# Keypad.net
KiCad netlist of a schematic drawn in Altium Designer
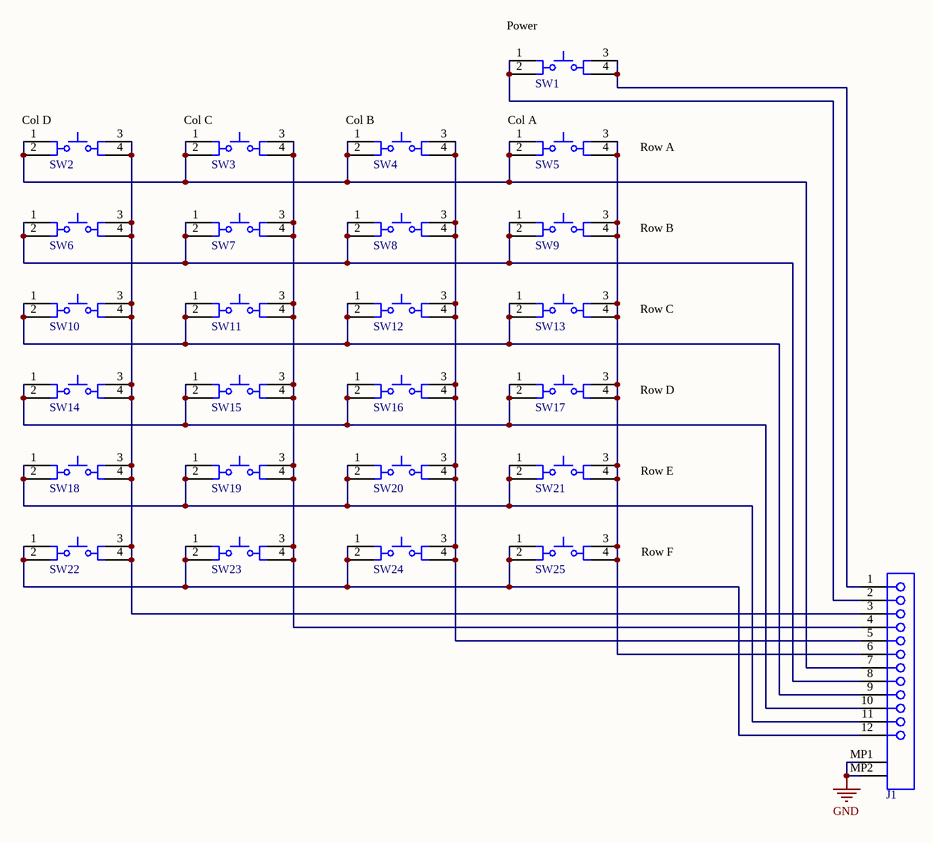
[diagram p0: Keypad.SchDoc]

(export (version "E")
  (design (tool "Eeschema 10.0.6"))
  (components
    (comp (ref "J1")
      (value "52271-1279")
      (footprint "MOLX-52271-1279")
      (fields (field (name "MANUFACTURER") "Molex"))
      (libsource (lib "Altium Content Vault") (part "CMP-1241-00238-1"))
    )
    (comp (ref "SW1")
      (value "4-1437565-1")
      (footprint "TECO-4-1437565-1_V")
      (description "Tactile Switch, 50 mA, 12 VDC, -20 to 85 degC, 4-Pin SMD, RoHS, Bulk")
      (fields (field (name "MANUFACTURER") "TEConnectivity/AMPBrand"))
      (libsource (lib "Altium Content Vault") (part "CMP-2000-05602-1"))
    )
    (comp (ref "SW2")
      (value "4-1437565-1")
      (footprint "TECO-4-1437565-1_V")
      (description "Tactile Switch, 50 mA, 12 VDC, -20 to 85 degC, 4-Pin SMD, RoHS, Bulk")
      (fields (field (name "MANUFACTURER") "TEConnectivity/AMPBrand"))
      (libsource (lib "Altium Content Vault") (part "CMP-2000-05602-1"))
    )
    (comp (ref "SW3")
      (value "4-1437565-1")
      (footprint "TECO-4-1437565-1_V")
      (description "Tactile Switch, 50 mA, 12 VDC, -20 to 85 degC, 4-Pin SMD, RoHS, Bulk")
      (fields (field (name "MANUFACTURER") "TEConnectivity/AMPBrand"))
      (libsource (lib "Altium Content Vault") (part "CMP-2000-05602-1"))
    )
    (comp (ref "SW4")
      (value "4-1437565-1")
      (footprint "TECO-4-1437565-1_V")
      (description "Tactile Switch, 50 mA, 12 VDC, -20 to 85 degC, 4-Pin SMD, RoHS, Bulk")
      (fields (field (name "MANUFACTURER") "TEConnectivity/AMPBrand"))
      (libsource (lib "Altium Content Vault") (part "CMP-2000-05602-1"))
    )
    (comp (ref "SW5")
      (value "4-1437565-1")
      (footprint "TECO-4-1437565-1_V")
      (description "Tactile Switch, 50 mA, 12 VDC, -20 to 85 degC, 4-Pin SMD, RoHS, Bulk")
      (fields (field (name "MANUFACTURER") "TEConnectivity/AMPBrand"))
      (libsource (lib "Altium Content Vault") (part "CMP-2000-05602-1"))
    )
    (comp (ref "SW6")
      (value "4-1437565-1")
      (footprint "TECO-4-1437565-1_V")
      (description "Tactile Switch, 50 mA, 12 VDC, -20 to 85 degC, 4-Pin SMD, RoHS, Bulk")
      (fields (field (name "MANUFACTURER") "TEConnectivity/AMPBrand"))
      (libsource (lib "Altium Content Vault") (part "CMP-2000-05602-1"))
    )
    (comp (ref "SW7")
      (value "4-1437565-1")
      (footprint "TECO-4-1437565-1_V")
      (description "Tactile Switch, 50 mA, 12 VDC, -20 to 85 degC, 4-Pin SMD, RoHS, Bulk")
      (fields (field (name "MANUFACTURER") "TEConnectivity/AMPBrand"))
      (libsource (lib "Altium Content Vault") (part "CMP-2000-05602-1"))
    )
    (comp (ref "SW8")
      (value "4-1437565-1")
      (footprint "TECO-4-1437565-1_V")
      (description "Tactile Switch, 50 mA, 12 VDC, -20 to 85 degC, 4-Pin SMD, RoHS, Bulk")
      (fields (field (name "MANUFACTURER") "TEConnectivity/AMPBrand"))
      (libsource (lib "Altium Content Vault") (part "CMP-2000-05602-1"))
    )
    (comp (ref "SW9")
      (value "4-1437565-1")
      (footprint "TECO-4-1437565-1_V")
      (description "Tactile Switch, 50 mA, 12 VDC, -20 to 85 degC, 4-Pin SMD, RoHS, Bulk")
      (fields (field (name "MANUFACTURER") "TEConnectivity/AMPBrand"))
      (libsource (lib "Altium Content Vault") (part "CMP-2000-05602-1"))
    )
    (comp (ref "SW10")
      (value "4-1437565-1")
      (footprint "TECO-4-1437565-1_V")
      (description "Tactile Switch, 50 mA, 12 VDC, -20 to 85 degC, 4-Pin SMD, RoHS, Bulk")
      (fields (field (name "MANUFACTURER") "TEConnectivity/AMPBrand"))
      (libsource (lib "Altium Content Vault") (part "CMP-2000-05602-1"))
    )
    (comp (ref "SW11")
      (value "4-1437565-1")
      (footprint "TECO-4-1437565-1_V")
      (description "Tactile Switch, 50 mA, 12 VDC, -20 to 85 degC, 4-Pin SMD, RoHS, Bulk")
      (fields (field (name "MANUFACTURER") "TEConnectivity/AMPBrand"))
      (libsource (lib "Altium Content Vault") (part "CMP-2000-05602-1"))
    )
    (comp (ref "SW12")
      (value "4-1437565-1")
      (footprint "TECO-4-1437565-1_V")
      (description "Tactile Switch, 50 mA, 12 VDC, -20 to 85 degC, 4-Pin SMD, RoHS, Bulk")
      (fields (field (name "MANUFACTURER") "TEConnectivity/AMPBrand"))
      (libsource (lib "Altium Content Vault") (part "CMP-2000-05602-1"))
    )
    (comp (ref "SW13")
      (value "4-1437565-1")
      (footprint "TECO-4-1437565-1_V")
      (description "Tactile Switch, 50 mA, 12 VDC, -20 to 85 degC, 4-Pin SMD, RoHS, Bulk")
      (fields (field (name "MANUFACTURER") "TEConnectivity/AMPBrand"))
      (libsource (lib "Altium Content Vault") (part "CMP-2000-05602-1"))
    )
    (comp (ref "SW14")
      (value "4-1437565-1")
      (footprint "TECO-4-1437565-1_V")
      (description "Tactile Switch, 50 mA, 12 VDC, -20 to 85 degC, 4-Pin SMD, RoHS, Bulk")
      (fields (field (name "MANUFACTURER") "TEConnectivity/AMPBrand"))
      (libsource (lib "Altium Content Vault") (part "CMP-2000-05602-1"))
    )
    (comp (ref "SW15")
      (value "4-1437565-1")
      (footprint "TECO-4-1437565-1_V")
      (description "Tactile Switch, 50 mA, 12 VDC, -20 to 85 degC, 4-Pin SMD, RoHS, Bulk")
      (fields (field (name "MANUFACTURER") "TEConnectivity/AMPBrand"))
      (libsource (lib "Altium Content Vault") (part "CMP-2000-05602-1"))
    )
    (comp (ref "SW16")
      (value "4-1437565-1")
      (footprint "TECO-4-1437565-1_V")
      (description "Tactile Switch, 50 mA, 12 VDC, -20 to 85 degC, 4-Pin SMD, RoHS, Bulk")
      (fields (field (name "MANUFACTURER") "TEConnectivity/AMPBrand"))
      (libsource (lib "Altium Content Vault") (part "CMP-2000-05602-1"))
    )
    (comp (ref "SW17")
      (value "4-1437565-1")
      (footprint "TECO-4-1437565-1_V")
      (description "Tactile Switch, 50 mA, 12 VDC, -20 to 85 degC, 4-Pin SMD, RoHS, Bulk")
      (fields (field (name "MANUFACTURER") "TEConnectivity/AMPBrand"))
      (libsource (lib "Altium Content Vault") (part "CMP-2000-05602-1"))
    )
    (comp (ref "SW18")
      (value "4-1437565-1")
      (footprint "TECO-4-1437565-1_V")
      (description "Tactile Switch, 50 mA, 12 VDC, -20 to 85 degC, 4-Pin SMD, RoHS, Bulk")
      (fields (field (name "MANUFACTURER") "TEConnectivity/AMPBrand"))
      (libsource (lib "Altium Content Vault") (part "CMP-2000-05602-1"))
    )
    (comp (ref "SW19")
      (value "4-1437565-1")
      (footprint "TECO-4-1437565-1_V")
      (description "Tactile Switch, 50 mA, 12 VDC, -20 to 85 degC, 4-Pin SMD, RoHS, Bulk")
      (fields (field (name "MANUFACTURER") "TEConnectivity/AMPBrand"))
      (libsource (lib "Altium Content Vault") (part "CMP-2000-05602-1"))
    )
    (comp (ref "SW20")
      (value "4-1437565-1")
      (footprint "TECO-4-1437565-1_V")
      (description "Tactile Switch, 50 mA, 12 VDC, -20 to 85 degC, 4-Pin SMD, RoHS, Bulk")
      (fields (field (name "MANUFACTURER") "TEConnectivity/AMPBrand"))
      (libsource (lib "Altium Content Vault") (part "CMP-2000-05602-1"))
    )
    (comp (ref "SW21")
      (value "4-1437565-1")
      (footprint "TECO-4-1437565-1_V")
      (description "Tactile Switch, 50 mA, 12 VDC, -20 to 85 degC, 4-Pin SMD, RoHS, Bulk")
      (fields (field (name "MANUFACTURER") "TEConnectivity/AMPBrand"))
      (libsource (lib "Altium Content Vault") (part "CMP-2000-05602-1"))
    )
    (comp (ref "SW22")
      (value "4-1437565-1")
      (footprint "TECO-4-1437565-1_V")
      (description "Tactile Switch, 50 mA, 12 VDC, -20 to 85 degC, 4-Pin SMD, RoHS, Bulk")
      (fields (field (name "MANUFACTURER") "TEConnectivity/AMPBrand"))
      (libsource (lib "Altium Content Vault") (part "CMP-2000-05602-1"))
    )
    (comp (ref "SW23")
      (value "4-1437565-1")
      (footprint "TECO-4-1437565-1_V")
      (description "Tactile Switch, 50 mA, 12 VDC, -20 to 85 degC, 4-Pin SMD, RoHS, Bulk")
      (fields (field (name "MANUFACTURER") "TEConnectivity/AMPBrand"))
      (libsource (lib "Altium Content Vault") (part "CMP-2000-05602-1"))
    )
    (comp (ref "SW24")
      (value "4-1437565-1")
      (footprint "TECO-4-1437565-1_V")
      (description "Tactile Switch, 50 mA, 12 VDC, -20 to 85 degC, 4-Pin SMD, RoHS, Bulk")
      (fields (field (name "MANUFACTURER") "TEConnectivity/AMPBrand"))
      (libsource (lib "Altium Content Vault") (part "CMP-2000-05602-1"))
    )
    (comp (ref "SW25")
      (value "4-1437565-1")
      (footprint "TECO-4-1437565-1_V")
      (description "Tactile Switch, 50 mA, 12 VDC, -20 to 85 degC, 4-Pin SMD, RoHS, Bulk")
      (fields (field (name "MANUFACTURER") "TEConnectivity/AMPBrand"))
      (libsource (lib "Altium Content Vault") (part "CMP-2000-05602-1"))
    )
  )
  (nets
    (net (code "1") (name "GND") (class "Default")
      (node (ref "J1") (pin "MP1") (pinfunction "MP1_MP1") (pintype "passive"))
      (node (ref "J1") (pin "MP2") (pinfunction "MP2_MP2") (pintype "passive"))
    )
    (net (code "2") (name "Net-(J1-Pad1)") (class "Default")
      (node (ref "J1") (pin "1") (pinfunction "1_1") (pintype "passive"))
      (node (ref "SW1") (pin "3") (pinfunction "3_3") (pintype "passive"))
      (node (ref "SW1") (pin "4") (pinfunction "4_4") (pintype "passive"))
    )
    (net (code "3") (name "Net-(J1-Pad2)") (class "Default")
      (node (ref "J1") (pin "2") (pinfunction "2_2") (pintype "passive"))
      (node (ref "SW1") (pin "1") (pinfunction "1_1") (pintype "passive"))
      (node (ref "SW1") (pin "2") (pinfunction "2_2") (pintype "passive"))
    )
    (net (code "4") (name "Net-(J1-Pad3)") (class "Default")
      (node (ref "J1") (pin "3") (pinfunction "3_3") (pintype "passive"))
      (node (ref "SW10") (pin "3") (pinfunction "3_3") (pintype "passive"))
      (node (ref "SW10") (pin "4") (pinfunction "4_4") (pintype "passive"))
      (node (ref "SW14") (pin "3") (pinfunction "3_3") (pintype "passive"))
      (node (ref "SW14") (pin "4") (pinfunction "4_4") (pintype "passive"))
      (node (ref "SW18") (pin "3") (pinfunction "3_3") (pintype "passive"))
      (node (ref "SW18") (pin "4") (pinfunction "4_4") (pintype "passive"))
      (node (ref "SW2") (pin "3") (pinfunction "3_3") (pintype "passive"))
      (node (ref "SW2") (pin "4") (pinfunction "4_4") (pintype "passive"))
      (node (ref "SW22") (pin "3") (pinfunction "3_3") (pintype "passive"))
      (node (ref "SW22") (pin "4") (pinfunction "4_4") (pintype "passive"))
      (node (ref "SW6") (pin "3") (pinfunction "3_3") (pintype "passive"))
      (node (ref "SW6") (pin "4") (pinfunction "4_4") (pintype "passive"))
    )
    (net (code "5") (name "Net-(J1-Pad4)") (class "Default")
      (node (ref "J1") (pin "4") (pinfunction "4_4") (pintype "passive"))
      (node (ref "SW11") (pin "3") (pinfunction "3_3") (pintype "passive"))
      (node (ref "SW11") (pin "4") (pinfunction "4_4") (pintype "passive"))
      (node (ref "SW15") (pin "3") (pinfunction "3_3") (pintype "passive"))
      (node (ref "SW15") (pin "4") (pinfunction "4_4") (pintype "passive"))
      (node (ref "SW19") (pin "3") (pinfunction "3_3") (pintype "passive"))
      (node (ref "SW19") (pin "4") (pinfunction "4_4") (pintype "passive"))
      (node (ref "SW23") (pin "3") (pinfunction "3_3") (pintype "passive"))
      (node (ref "SW23") (pin "4") (pinfunction "4_4") (pintype "passive"))
      (node (ref "SW3") (pin "3") (pinfunction "3_3") (pintype "passive"))
      (node (ref "SW3") (pin "4") (pinfunction "4_4") (pintype "passive"))
      (node (ref "SW7") (pin "3") (pinfunction "3_3") (pintype "passive"))
      (node (ref "SW7") (pin "4") (pinfunction "4_4") (pintype "passive"))
    )
    (net (code "6") (name "Net-(J1-Pad5)") (class "Default")
      (node (ref "J1") (pin "5") (pinfunction "5_5") (pintype "passive"))
      (node (ref "SW12") (pin "3") (pinfunction "3_3") (pintype "passive"))
      (node (ref "SW12") (pin "4") (pinfunction "4_4") (pintype "passive"))
      (node (ref "SW16") (pin "3") (pinfunction "3_3") (pintype "passive"))
      (node (ref "SW16") (pin "4") (pinfunction "4_4") (pintype "passive"))
      (node (ref "SW20") (pin "3") (pinfunction "3_3") (pintype "passive"))
      (node (ref "SW20") (pin "4") (pinfunction "4_4") (pintype "passive"))
      (node (ref "SW24") (pin "3") (pinfunction "3_3") (pintype "passive"))
      (node (ref "SW24") (pin "4") (pinfunction "4_4") (pintype "passive"))
      (node (ref "SW4") (pin "3") (pinfunction "3_3") (pintype "passive"))
      (node (ref "SW4") (pin "4") (pinfunction "4_4") (pintype "passive"))
      (node (ref "SW8") (pin "3") (pinfunction "3_3") (pintype "passive"))
      (node (ref "SW8") (pin "4") (pinfunction "4_4") (pintype "passive"))
    )
    (net (code "7") (name "Net-(J1-Pad6)") (class "Default")
      (node (ref "J1") (pin "6") (pinfunction "6_6") (pintype "passive"))
      (node (ref "SW13") (pin "3") (pinfunction "3_3") (pintype "passive"))
      (node (ref "SW13") (pin "4") (pinfunction "4_4") (pintype "passive"))
      (node (ref "SW17") (pin "3") (pinfunction "3_3") (pintype "passive"))
      (node (ref "SW17") (pin "4") (pinfunction "4_4") (pintype "passive"))
      (node (ref "SW21") (pin "3") (pinfunction "3_3") (pintype "passive"))
      (node (ref "SW21") (pin "4") (pinfunction "4_4") (pintype "passive"))
      (node (ref "SW25") (pin "3") (pinfunction "3_3") (pintype "passive"))
      (node (ref "SW25") (pin "4") (pinfunction "4_4") (pintype "passive"))
      (node (ref "SW5") (pin "3") (pinfunction "3_3") (pintype "passive"))
      (node (ref "SW5") (pin "4") (pinfunction "4_4") (pintype "passive"))
      (node (ref "SW9") (pin "3") (pinfunction "3_3") (pintype "passive"))
      (node (ref "SW9") (pin "4") (pinfunction "4_4") (pintype "passive"))
    )
    (net (code "8") (name "Net-(J1-Pad7)") (class "Default")
      (node (ref "J1") (pin "7") (pinfunction "7_7") (pintype "passive"))
      (node (ref "SW2") (pin "1") (pinfunction "1_1") (pintype "passive"))
      (node (ref "SW2") (pin "2") (pinfunction "2_2") (pintype "passive"))
      (node (ref "SW3") (pin "1") (pinfunction "1_1") (pintype "passive"))
      (node (ref "SW3") (pin "2") (pinfunction "2_2") (pintype "passive"))
      (node (ref "SW4") (pin "1") (pinfunction "1_1") (pintype "passive"))
      (node (ref "SW4") (pin "2") (pinfunction "2_2") (pintype "passive"))
      (node (ref "SW5") (pin "1") (pinfunction "1_1") (pintype "passive"))
      (node (ref "SW5") (pin "2") (pinfunction "2_2") (pintype "passive"))
    )
    (net (code "9") (name "Net-(J1-Pad8)") (class "Default")
      (node (ref "J1") (pin "8") (pinfunction "8_8") (pintype "passive"))
      (node (ref "SW6") (pin "1") (pinfunction "1_1") (pintype "passive"))
      (node (ref "SW6") (pin "2") (pinfunction "2_2") (pintype "passive"))
      (node (ref "SW7") (pin "1") (pinfunction "1_1") (pintype "passive"))
      (node (ref "SW7") (pin "2") (pinfunction "2_2") (pintype "passive"))
      (node (ref "SW8") (pin "1") (pinfunction "1_1") (pintype "passive"))
      (node (ref "SW8") (pin "2") (pinfunction "2_2") (pintype "passive"))
      (node (ref "SW9") (pin "1") (pinfunction "1_1") (pintype "passive"))
      (node (ref "SW9") (pin "2") (pinfunction "2_2") (pintype "passive"))
    )
    (net (code "10") (name "Net-(J1-Pad9)") (class "Default")
      (node (ref "J1") (pin "9") (pinfunction "9_9") (pintype "passive"))
      (node (ref "SW10") (pin "1") (pinfunction "1_1") (pintype "passive"))
      (node (ref "SW10") (pin "2") (pinfunction "2_2") (pintype "passive"))
      (node (ref "SW11") (pin "1") (pinfunction "1_1") (pintype "passive"))
      (node (ref "SW11") (pin "2") (pinfunction "2_2") (pintype "passive"))
      (node (ref "SW12") (pin "1") (pinfunction "1_1") (pintype "passive"))
      (node (ref "SW12") (pin "2") (pinfunction "2_2") (pintype "passive"))
      (node (ref "SW13") (pin "1") (pinfunction "1_1") (pintype "passive"))
      (node (ref "SW13") (pin "2") (pinfunction "2_2") (pintype "passive"))
    )
    (net (code "11") (name "Net-(J1-Pad10)") (class "Default")
      (node (ref "J1") (pin "10") (pinfunction "10_10") (pintype "passive"))
      (node (ref "SW14") (pin "1") (pinfunction "1_1") (pintype "passive"))
      (node (ref "SW14") (pin "2") (pinfunction "2_2") (pintype "passive"))
      (node (ref "SW15") (pin "1") (pinfunction "1_1") (pintype "passive"))
      (node (ref "SW15") (pin "2") (pinfunction "2_2") (pintype "passive"))
      (node (ref "SW16") (pin "1") (pinfunction "1_1") (pintype "passive"))
      (node (ref "SW16") (pin "2") (pinfunction "2_2") (pintype "passive"))
      (node (ref "SW17") (pin "1") (pinfunction "1_1") (pintype "passive"))
      (node (ref "SW17") (pin "2") (pinfunction "2_2") (pintype "passive"))
    )
    (net (code "12") (name "Net-(J1-Pad11)") (class "Default")
      (node (ref "J1") (pin "11") (pinfunction "11_11") (pintype "passive"))
      (node (ref "SW18") (pin "1") (pinfunction "1_1") (pintype "passive"))
      (node (ref "SW18") (pin "2") (pinfunction "2_2") (pintype "passive"))
      (node (ref "SW19") (pin "1") (pinfunction "1_1") (pintype "passive"))
      (node (ref "SW19") (pin "2") (pinfunction "2_2") (pintype "passive"))
      (node (ref "SW20") (pin "1") (pinfunction "1_1") (pintype "passive"))
      (node (ref "SW20") (pin "2") (pinfunction "2_2") (pintype "passive"))
      (node (ref "SW21") (pin "1") (pinfunction "1_1") (pintype "passive"))
      (node (ref "SW21") (pin "2") (pinfunction "2_2") (pintype "passive"))
    )
    (net (code "13") (name "Net-(J1-Pad12)") (class "Default")
      (node (ref "J1") (pin "12") (pinfunction "12_12") (pintype "passive"))
      (node (ref "SW22") (pin "1") (pinfunction "1_1") (pintype "passive"))
      (node (ref "SW22") (pin "2") (pinfunction "2_2") (pintype "passive"))
      (node (ref "SW23") (pin "1") (pinfunction "1_1") (pintype "passive"))
      (node (ref "SW23") (pin "2") (pinfunction "2_2") (pintype "passive"))
      (node (ref "SW24") (pin "1") (pinfunction "1_1") (pintype "passive"))
      (node (ref "SW24") (pin "2") (pinfunction "2_2") (pintype "passive"))
      (node (ref "SW25") (pin "1") (pinfunction "1_1") (pintype "passive"))
      (node (ref "SW25") (pin "2") (pinfunction "2_2") (pintype "passive"))
    )
  )
)
